# Charger.net
KiCad netlist of a schematic drawn in Altium Designer
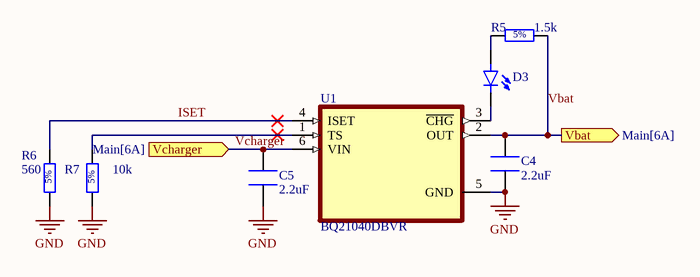
[diagram p0: Charger.SchDoc]

(export (version "E")
  (design (tool "Eeschema 10.0.6"))
  (components
    (comp (ref "C4")
      (value "2.2uF")
      (footprint "APSS Prototype Parts:CAPACITOR_0805_2012M-70N")
      (fields
        (field (name "TOLERANCE") "±10%")
        (field (name "MF PART NO.") "C0805C225K8PACTU")
        (field (name "APSS STANDARD PART") "APSS Standard")
      )
      (libsource (lib "APSS Prototype Parts") (part "C0805C225K8PACTU"))
    )
    (comp (ref "C5")
      (value "2.2uF")
      (footprint "APSS Prototype Parts:CAPACITOR_0805_2012M-70N")
      (fields
        (field (name "TOLERANCE") "±10%")
        (field (name "MF PART NO.") "C0805C225K8PACTU")
        (field (name "APSS STANDARD PART") "APSS Standard")
      )
      (libsource (lib "APSS Prototype Parts") (part "C0805C225K8PACTU"))
    )
    (comp (ref "D3")
      (value "LTST-C190 Series")
      (footprint "APSS Prototype Parts:LED_0603_1608M_0.80mm")
      (description "Diode - LED, 0603")
      (fields (field (name "APSS STANDARD PART") "APSS Standard"))
      (libsource (lib "APSS Prototype Parts") (part "LTST-C190 Series"))
    )
    (comp (ref "R5")
      (value "1.5k")
      (footprint "APSS Prototype Parts:Resistor_0805_2012M-50N")
      (fields
        (field (name "TOLERANCE") "5%")
        (field (name "POWER") "1/8W")
        (field (name "APSS STANDARD PART") "APSS Standard")
      )
      (libsource (lib "") (part "RMCF0805JT Series_1"))
    )
    (comp (ref "R6")
      (value "560")
      (footprint "APSS Prototype Parts:Resistor_0805_2012M-50N")
      (fields
        (field (name "TOLERANCE") "5%")
        (field (name "POWER") "1/8W")
        (field (name "APSS STANDARD PART") "APSS Standard")
      )
      (libsource (lib "APSS Prototype Parts") (part "RMCF0805JT Series"))
    )
    (comp (ref "R7")
      (value "10k")
      (footprint "APSS Prototype Parts:Resistor_0805_2012M-50N")
      (fields
        (field (name "TOLERANCE") "5%")
        (field (name "POWER") "1/8W")
        (field (name "APSS STANDARD PART") "APSS Standard")
      )
      (libsource (lib "APSS Prototype Parts") (part "RMCF0805JT Series"))
    )
    (comp (ref "U1")
      (value "BQ21040DBVR")
      (footprint "SOT95P280X145-6N")
      (description "1-cell, 0.8-A Li-ion and Li-polymer battery charger")
      (fields (field (name "MF") "Texas Instruments"))
      (libsource (lib "BQ21040DBVR") (part "BQ21040DBVR"))
    )
  )
  (nets
    (net (code "1") (name "/ISET") (class "Default")
      (node (ref "R6") (pin "2") (pinfunction "2_2") (pintype "passive"))
      (node (ref "U1") (pin "4") (pinfunction "ISET_4") (pintype "input"))
    )
    (net (code "2") (name "/Vbat") (class "Default")
      (node (ref "C4") (pin "2") (pinfunction "2_2") (pintype "passive"))
      (node (ref "R5") (pin "2") (pinfunction "2_2") (pintype "passive"))
      (node (ref "U1") (pin "2") (pinfunction "OUT_2") (pintype "output"))
    )
    (net (code "3") (name "/Vcharger") (class "Default")
      (node (ref "C5") (pin "2") (pinfunction "2_2") (pintype "passive"))
      (node (ref "U1") (pin "6") (pinfunction "VIN_6") (pintype "input"))
    )
    (net (code "4") (name "GND") (class "Default")
      (node (ref "C4") (pin "1") (pinfunction "1_1") (pintype "passive"))
      (node (ref "C5") (pin "1") (pinfunction "1_1") (pintype "passive"))
      (node (ref "R6") (pin "1") (pinfunction "1_1") (pintype "passive"))
      (node (ref "R7") (pin "1") (pinfunction "1_1") (pintype "passive"))
      (node (ref "U1") (pin "5") (pinfunction "GND_5") (pintype "power_in"))
    )
    (net (code "5") (name "Net-(D3-PadA)") (class "Default")
      (node (ref "D3") (pin "A") (pinfunction "A_A") (pintype "passive"))
      (node (ref "R5") (pin "1") (pinfunction "1_1") (pintype "passive"))
    )
    (net (code "6") (name "Net-(U1-TS)") (class "Default")
      (node (ref "R7") (pin "2") (pinfunction "2_2") (pintype "passive"))
      (node (ref "U1") (pin "1") (pinfunction "TS_1") (pintype "input"))
    )
    (net (code "7") (name "Net-(U1-~{CHG})") (class "Default")
      (node (ref "D3") (pin "C") (pinfunction "C_C") (pintype "passive"))
      (node (ref "U1") (pin "3") (pinfunction "~{CHG}_3") (pintype "output"))
    )
  )
)
